# ZHSD-ETHERNET.net
KiCad netlist of a schematic drawn in Altium Designer
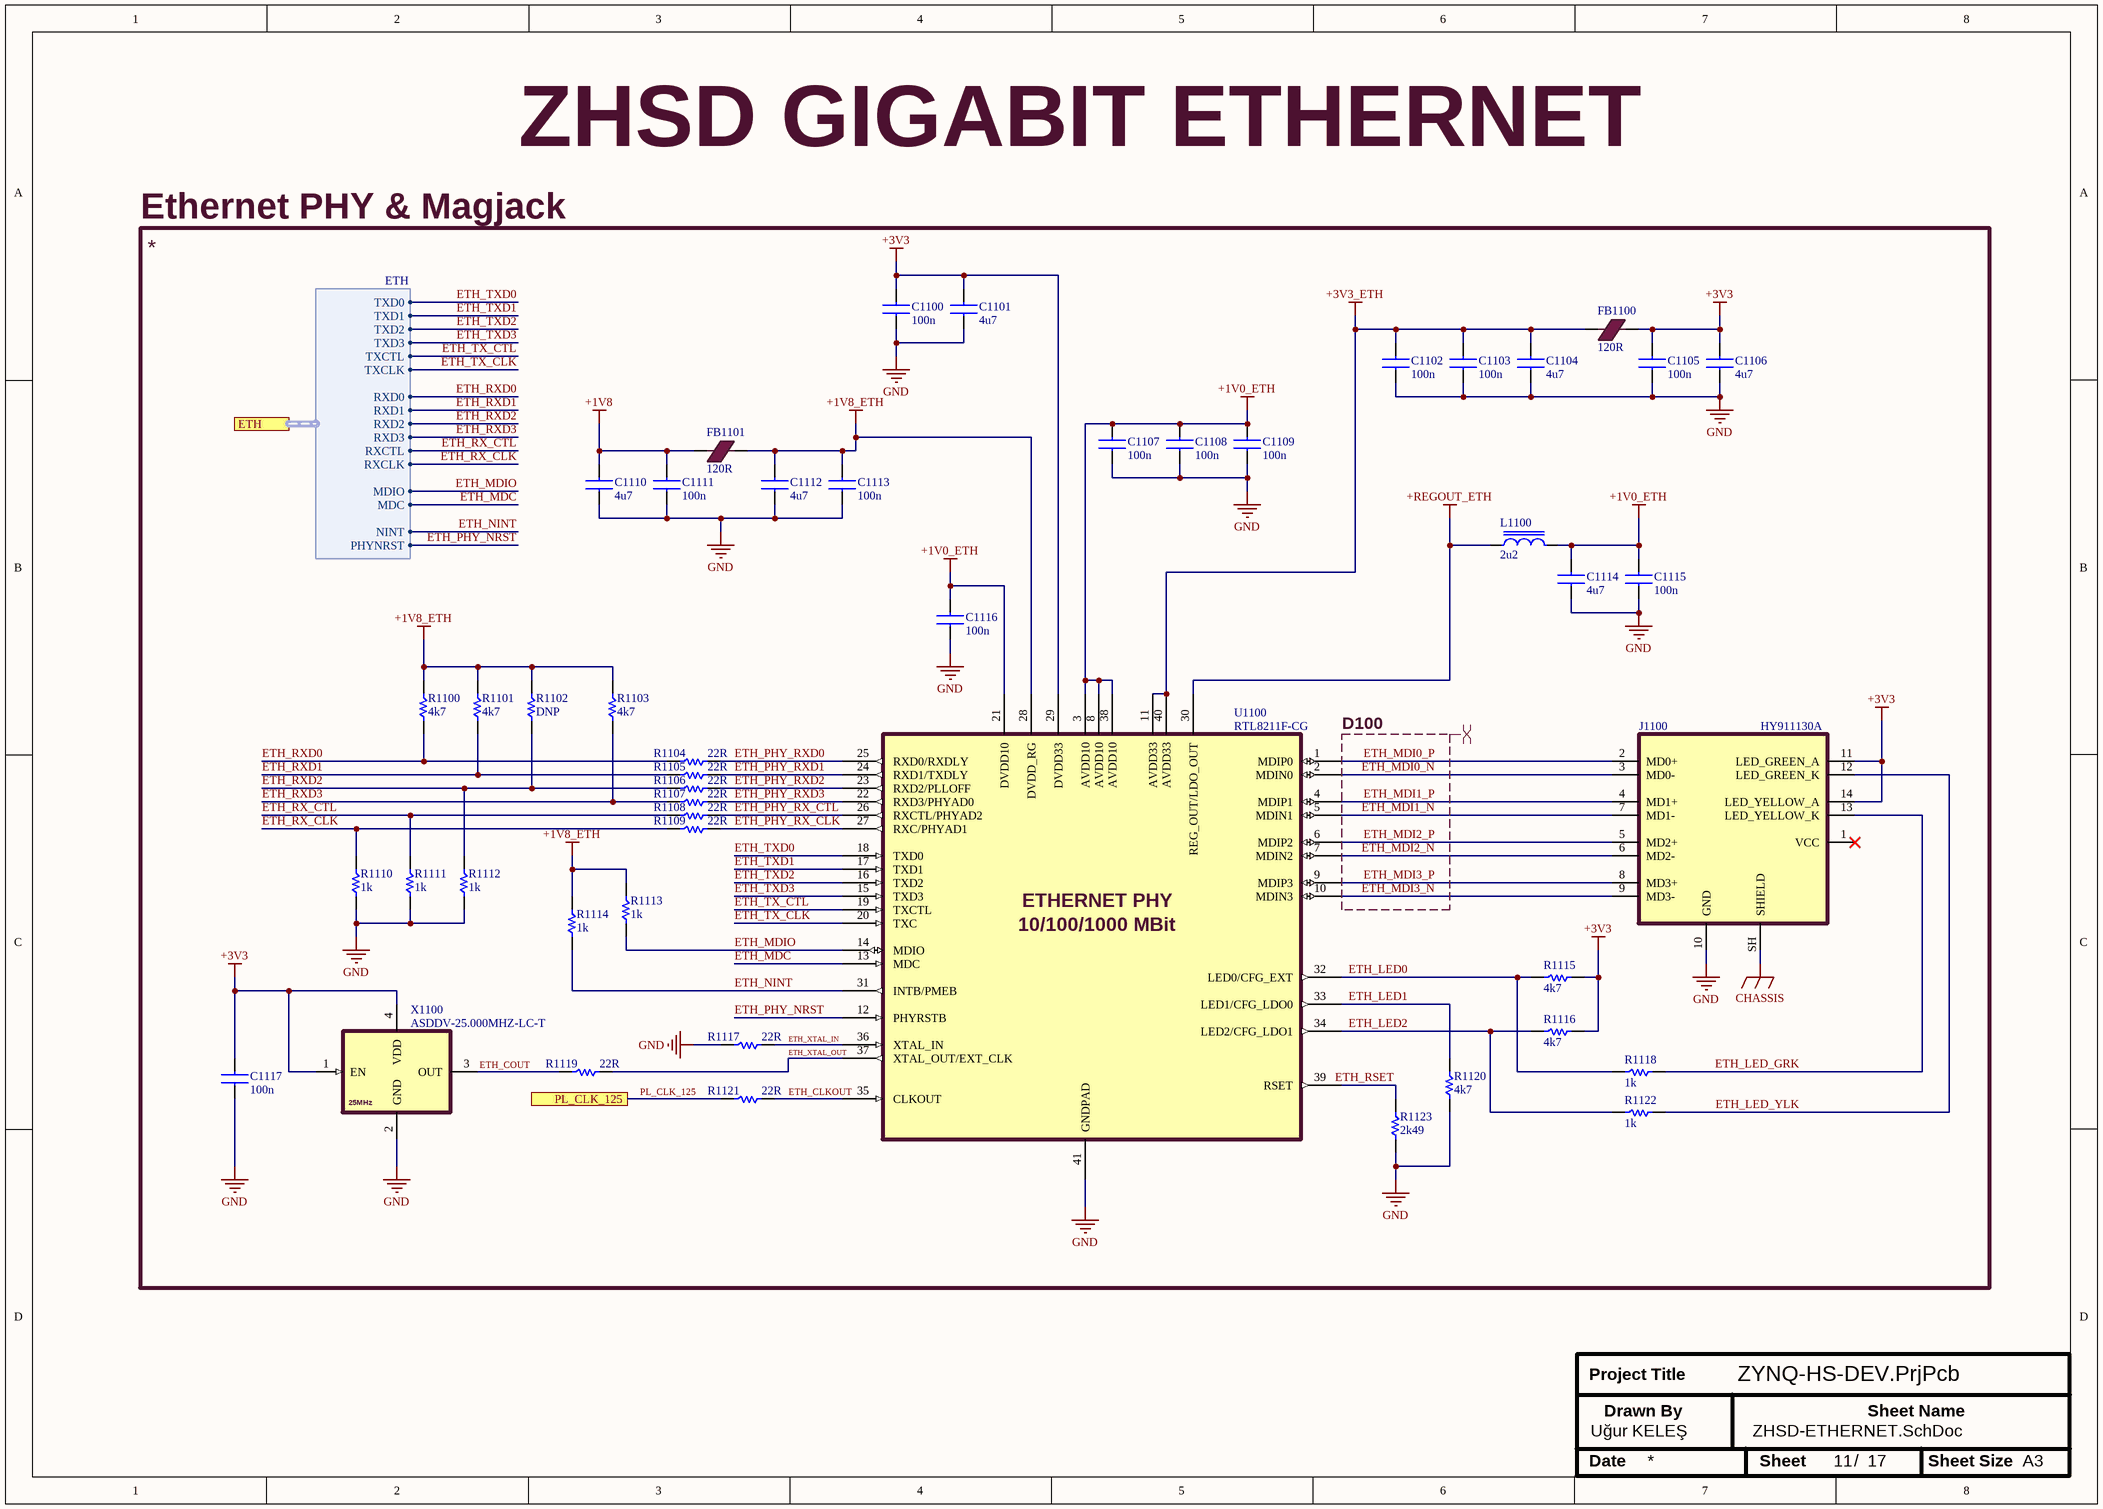
[diagram p0: ZHSD-ETHERNET.SchDoc]

(export (version "E")
  (design (tool "Eeschema 10.0.6"))
  (components
    (comp (ref "C1100")
      (value "100n")
      (footprint "0603CAPC1608X09N")
      (description "CAP CER 0.1UF 16V X7R 0402 (1005) ±10%")
      (fields (field (name "MANUFACTURER") "Murata Electronics") (field (name "MPN") "GRM155R71C104KA88J"))
      (libsource (lib "UK_Library") (part "GRM155R71C104KA88J"))
    )
    (comp (ref "C1101")
      (value "4u7")
      (footprint "0603CAPC1608X09N")
      (description "CAP CER 4.7UF 10V X5R 0603 (1608) ±10%")
      (fields
        (field (name "MANUFACTURER") "Samsung Electro-Mechanics")
        (field (name "MPN") "CL10A475KP8NNNC")
      )
      (libsource (lib "UK_Library") (part "CL10A475KP8NNNC"))
    )
    (comp (ref "C1102")
      (value "100n")
      (footprint "0603CAPC1608X09N")
      (description "CAP CER 0.1UF 16V X7R 0402 (1005) ±10%")
      (fields (field (name "MANUFACTURER") "Murata Electronics") (field (name "MPN") "GRM155R71C104KA88J"))
      (libsource (lib "UK_Library") (part "GRM155R71C104KA88J"))
    )
    (comp (ref "C1103")
      (value "100n")
      (footprint "0603CAPC1608X09N")
      (description "CAP CER 0.1UF 16V X7R 0402 (1005) ±10%")
      (fields (field (name "MANUFACTURER") "Murata Electronics") (field (name "MPN") "GRM155R71C104KA88J"))
      (libsource (lib "UK_Library") (part "GRM155R71C104KA88J"))
    )
    (comp (ref "C1104")
      (value "4u7")
      (footprint "0603CAPC1608X09N")
      (description "CAP CER 4.7UF 10V X5R 0603 (1608) ±10%")
      (fields
        (field (name "MANUFACTURER") "Samsung Electro-Mechanics")
        (field (name "MPN") "CL10A475KP8NNNC")
      )
      (libsource (lib "UK_Library") (part "CL10A475KP8NNNC"))
    )
    (comp (ref "C1105")
      (value "100n")
      (footprint "0603CAPC1608X09N")
      (description "CAP CER 0.1UF 16V X7R 0402 (1005) ±10%")
      (fields (field (name "MANUFACTURER") "Murata Electronics") (field (name "MPN") "GRM155R71C104KA88J"))
      (libsource (lib "UK_Library") (part "GRM155R71C104KA88J"))
    )
    (comp (ref "C1106")
      (value "4u7")
      (footprint "0603CAPC1608X09N")
      (description "CAP CER 4.7UF 10V X5R 0603 (1608) ±10%")
      (fields
        (field (name "MANUFACTURER") "Samsung Electro-Mechanics")
        (field (name "MPN") "CL10A475KP8NNNC")
      )
      (libsource (lib "UK_Library") (part "CL10A475KP8NNNC"))
    )
    (comp (ref "C1107")
      (value "100n")
      (footprint "0603CAPC1608X09N")
      (description "CAP CER 0.1UF 16V X7R 0402 (1005) ±10%")
      (fields (field (name "MANUFACTURER") "Murata Electronics") (field (name "MPN") "GRM155R71C104KA88J"))
      (libsource (lib "UK_Library") (part "GRM155R71C104KA88J"))
    )
    (comp (ref "C1108")
      (value "100n")
      (footprint "0603CAPC1608X09N")
      (description "CAP CER 0.1UF 16V X7R 0402 (1005) ±10%")
      (fields (field (name "MANUFACTURER") "Murata Electronics") (field (name "MPN") "GRM155R71C104KA88J"))
      (libsource (lib "UK_Library") (part "GRM155R71C104KA88J"))
    )
    (comp (ref "C1109")
      (value "100n")
      (footprint "0603CAPC1608X09N")
      (description "CAP CER 0.1UF 16V X7R 0402 (1005) ±10%")
      (fields (field (name "MANUFACTURER") "Murata Electronics") (field (name "MPN") "GRM155R71C104KA88J"))
      (libsource (lib "UK_Library") (part "GRM155R71C104KA88J"))
    )
    (comp (ref "C1110")
      (value "4u7")
      (footprint "0603CAPC1608X09N")
      (description "CAP CER 4.7UF 10V X5R 0603 (1608) ±10%")
      (fields
        (field (name "MANUFACTURER") "Samsung Electro-Mechanics")
        (field (name "MPN") "CL10A475KP8NNNC")
      )
      (libsource (lib "UK_Library") (part "CL10A475KP8NNNC"))
    )
    (comp (ref "C1111")
      (value "100n")
      (footprint "0603CAPC1608X09N")
      (description "CAP CER 0.1UF 16V X7R 0402 (1005) ±10%")
      (fields (field (name "MANUFACTURER") "Murata Electronics") (field (name "MPN") "GRM155R71C104KA88J"))
      (libsource (lib "UK_Library") (part "GRM155R71C104KA88J"))
    )
    (comp (ref "C1112")
      (value "4u7")
      (footprint "0603CAPC1608X09N")
      (description "CAP CER 4.7UF 10V X5R 0603 (1608) ±10%")
      (fields
        (field (name "MANUFACTURER") "Samsung Electro-Mechanics")
        (field (name "MPN") "CL10A475KP8NNNC")
      )
      (libsource (lib "UK_Library") (part "CL10A475KP8NNNC"))
    )
    (comp (ref "C1113")
      (value "100n")
      (footprint "0603CAPC1608X09N")
      (description "CAP CER 0.1UF 16V X7R 0402 (1005) ±10%")
      (fields (field (name "MANUFACTURER") "Murata Electronics") (field (name "MPN") "GRM155R71C104KA88J"))
      (libsource (lib "UK_Library") (part "GRM155R71C104KA88J"))
    )
    (comp (ref "C1114")
      (value "4u7")
      (footprint "0603CAPC1608X09N")
      (description "CAP CER 4.7UF 10V X5R 0603 (1608) ±10%")
      (fields
        (field (name "MANUFACTURER") "Samsung Electro-Mechanics")
        (field (name "MPN") "CL10A475KP8NNNC")
      )
      (libsource (lib "UK_Library") (part "CL10A475KP8NNNC"))
    )
    (comp (ref "C1115")
      (value "100n")
      (footprint "0603CAPC1608X09N")
      (description "CAP CER 0.1UF 16V X7R 0402 (1005) ±10%")
      (fields (field (name "MANUFACTURER") "Murata Electronics") (field (name "MPN") "GRM155R71C104KA88J"))
      (libsource (lib "UK_Library") (part "GRM155R71C104KA88J"))
    )
    (comp (ref "C1116")
      (value "100n")
      (footprint "0603CAPC1608X09N")
      (description "CAP CER 0.1UF 16V X7R 0402 (1005) ±10%")
      (fields (field (name "MANUFACTURER") "Murata Electronics") (field (name "MPN") "GRM155R71C104KA88J"))
      (libsource (lib "UK_Library") (part "GRM155R71C104KA88J"))
    )
    (comp (ref "C1117")
      (value "100n")
      (footprint "0603CAPC1608X09N")
      (description "CAP CER 0.1UF 50V X7R 0603 (1608) ±10%")
      (fields (field (name "MANUFACTURER") "KEMET") (field (name "MPN") "C0603C104K5RACTU"))
      (libsource (lib "UK_Library") (part "C0603C104K5RACTU"))
    )
    (comp (ref "FB1100")
      (value "120R")
      (footprint "0603INDC1608X08N")
      (description "FERRITE BEAD 120 OHM 0603 (1608) 3A 25mOhm")
      (fields (field (name "MANUFACTURER") "Murata Electronics") (field (name "MPN") "BLM18SG121TN1D"))
      (libsource (lib "UK_Library") (part "BLM18SG121TN1D"))
    )
    (comp (ref "FB1101")
      (value "120R")
      (footprint "0603INDC1608X08N")
      (description "FERRITE BEAD 120 OHM 0603 (1608) 3A 25mOhm")
      (fields (field (name "MANUFACTURER") "Murata Electronics") (field (name "MPN") "BLM18SG121TN1D"))
      (libsource (lib "UK_Library") (part "BLM18SG121TN1D"))
    )
    (comp (ref "J1100")
      (value "HY911130A")
      (footprint "HY911130A")
      (description "Jack Modular Connector RJ45 Through Hole Shielded")
      (fields (field (name "MANUFACTURER") "Hanrun"))
      (libsource (lib "UK_Library") (part "HY911130A"))
    )
    (comp (ref "L1100")
      (value "2u2")
      (footprint "0603INDC1608X08N")
      (description "FIXED IND 2.2UH 1.05A 250 MOHM 0603 (1608 Metric)")
      (fields (field (name "MANUFACTURER") "Murata Electronics") (field (name "MPN") "LQM18PN2R2MGHD"))
      (libsource (lib "UK_Library") (part "LQM18PN2R2MGHD"))
    )
    (comp (ref "R1100")
      (value "4k7")
      (footprint "0402RESC1005X04N")
      (description "RES 4.7K OHM 5% 1/16W 0402 (1005)")
      (fields (field (name "MANUFACTURER") "YAGEO") (field (name "MPN") "RT0402FRE0780RL"))
      (libsource (lib "UK_Library") (part "RC0402JR-074K7L"))
    )
    (comp (ref "R1101")
      (value "4k7")
      (footprint "0402RESC1005X04N")
      (description "RES 4.7K OHM 5% 1/16W 0402 (1005)")
      (fields (field (name "MANUFACTURER") "YAGEO") (field (name "MPN") "RT0402FRE0780RL"))
      (libsource (lib "UK_Library") (part "RC0402JR-074K7L"))
    )
    (comp (ref "R1102")
      (value "DNP")
      (footprint "0402RESC1005X04N")
      (description "DO NOT POPULATE RESISTOR")
      (fields (field (name "MANUFACTURER") "***"))
      (libsource (lib "UK_Library") (part "DNP_RES"))
    )
    (comp (ref "R1103")
      (value "4k7")
      (footprint "0402RESC1005X04N")
      (description "RES 4.7K OHM 5% 1/16W 0402 (1005)")
      (fields (field (name "MANUFACTURER") "YAGEO") (field (name "MPN") "RT0402FRE0780RL"))
      (libsource (lib "UK_Library") (part "RC0402JR-074K7L"))
    )
    (comp (ref "R1104")
      (value "22R")
      (footprint "0603RESC1608X05N")
      (description "RES 22 OHM 1% 1/10W 0603 (1608)")
      (fields (field (name "MANUFACTURER") "YAGEO") (field (name "MPN") "RC0603FR-0722RL"))
      (libsource (lib "UK_Library") (part "RC0603FR-0722RL"))
    )
    (comp (ref "R1105")
      (value "22R")
      (footprint "0603RESC1608X05N")
      (description "RES 22 OHM 1% 1/10W 0603 (1608)")
      (fields (field (name "MANUFACTURER") "YAGEO") (field (name "MPN") "RC0603FR-0722RL"))
      (libsource (lib "UK_Library") (part "RC0603FR-0722RL"))
    )
    (comp (ref "R1106")
      (value "22R")
      (footprint "0603RESC1608X05N")
      (description "RES 22 OHM 1% 1/10W 0603 (1608)")
      (fields (field (name "MANUFACTURER") "YAGEO") (field (name "MPN") "RC0603FR-0722RL"))
      (libsource (lib "UK_Library") (part "RC0603FR-0722RL"))
    )
    (comp (ref "R1107")
      (value "22R")
      (footprint "0603RESC1608X05N")
      (description "RES 22 OHM 1% 1/10W 0603 (1608)")
      (fields (field (name "MANUFACTURER") "YAGEO") (field (name "MPN") "RC0603FR-0722RL"))
      (libsource (lib "UK_Library") (part "RC0603FR-0722RL"))
    )
    (comp (ref "R1108")
      (value "22R")
      (footprint "0603RESC1608X05N")
      (description "RES 22 OHM 1% 1/10W 0603 (1608)")
      (fields (field (name "MANUFACTURER") "YAGEO") (field (name "MPN") "RC0603FR-0722RL"))
      (libsource (lib "UK_Library") (part "RC0603FR-0722RL"))
    )
    (comp (ref "R1109")
      (value "22R")
      (footprint "0603RESC1608X05N")
      (description "RES 22 OHM 1% 1/10W 0603 (1608)")
      (fields (field (name "MANUFACTURER") "YAGEO") (field (name "MPN") "RC0603FR-0722RL"))
      (libsource (lib "UK_Library") (part "RC0603FR-0722RL"))
    )
    (comp (ref "R1110")
      (value "1k")
      (footprint "0402RESC1005X04N")
      (description "RES 1K OHM 5% 1/16W 0402 (1005)")
      (fields (field (name "MANUFACTURER") "YAGEO") (field (name "MPN") "RC0402JR-071KL"))
      (libsource (lib "UK_Library") (part "RC0402JR-071KL"))
    )
    (comp (ref "R1111")
      (value "1k")
      (footprint "0402RESC1005X04N")
      (description "RES 1K OHM 5% 1/16W 0402 (1005)")
      (fields (field (name "MANUFACTURER") "YAGEO") (field (name "MPN") "RC0402JR-071KL"))
      (libsource (lib "UK_Library") (part "RC0402JR-071KL"))
    )
    (comp (ref "R1112")
      (value "1k")
      (footprint "0402RESC1005X04N")
      (description "RES 1K OHM 5% 1/16W 0402 (1005)")
      (fields (field (name "MANUFACTURER") "YAGEO") (field (name "MPN") "RC0402JR-071KL"))
      (libsource (lib "UK_Library") (part "RC0402JR-071KL"))
    )
    (comp (ref "R1113")
      (value "1k")
      (footprint "0402RESC1005X04N")
      (description "RES 1K OHM 5% 1/16W 0402 (1005)")
      (fields (field (name "MANUFACTURER") "YAGEO") (field (name "MPN") "RC0402JR-071KL"))
      (libsource (lib "UK_Library") (part "RC0402JR-071KL"))
    )
    (comp (ref "R1114")
      (value "1k")
      (footprint "0402RESC1005X04N")
      (description "RES 1K OHM 5% 1/16W 0402 (1005)")
      (fields (field (name "MANUFACTURER") "YAGEO") (field (name "MPN") "RC0402JR-071KL"))
      (libsource (lib "UK_Library") (part "RC0402JR-071KL"))
    )
    (comp (ref "R1115")
      (value "4k7")
      (footprint "0402RESC1005X04N")
      (description "RES 4.7K OHM 5% 1/16W 0402 (1005)")
      (fields (field (name "MANUFACTURER") "YAGEO") (field (name "MPN") "RT0402FRE0780RL"))
      (libsource (lib "UK_Library") (part "RC0402JR-074K7L"))
    )
    (comp (ref "R1116")
      (value "4k7")
      (footprint "0402RESC1005X04N")
      (description "RES 4.7K OHM 5% 1/16W 0402 (1005)")
      (fields (field (name "MANUFACTURER") "YAGEO") (field (name "MPN") "RT0402FRE0780RL"))
      (libsource (lib "UK_Library") (part "RC0402JR-074K7L"))
    )
    (comp (ref "R1117")
      (value "22R")
      (footprint "0603RESC1608X05N")
      (description "RES 22 OHM 1% 1/10W 0603 (1608)")
      (fields (field (name "MANUFACTURER") "YAGEO") (field (name "MPN") "RC0603FR-0722RL"))
      (libsource (lib "UK_Library") (part "RC0603FR-0722RL"))
    )
    (comp (ref "R1118")
      (value "1k")
      (footprint "0402RESC1005X04N")
      (description "RES 1K OHM 5% 1/16W 0402 (1005)")
      (fields (field (name "MANUFACTURER") "YAGEO") (field (name "MPN") "RC0402JR-071KL"))
      (libsource (lib "UK_Library") (part "RC0402JR-071KL"))
    )
    (comp (ref "R1119")
      (value "22R")
      (footprint "0603RESC1608X05N")
      (description "RES 22 OHM 1% 1/10W 0603 (1608)")
      (fields (field (name "MANUFACTURER") "YAGEO") (field (name "MPN") "RC0603FR-0722RL"))
      (libsource (lib "UK_Library") (part "RC0603FR-0722RL"))
    )
    (comp (ref "R1120")
      (value "4k7")
      (footprint "0402RESC1005X04N")
      (description "RES 4.7K OHM 5% 1/16W 0402 (1005)")
      (fields (field (name "MANUFACTURER") "YAGEO") (field (name "MPN") "RT0402FRE0780RL"))
      (libsource (lib "UK_Library") (part "RC0402JR-074K7L"))
    )
    (comp (ref "R1121")
      (value "22R")
      (footprint "0603RESC1608X05N")
      (description "RES 22 OHM 1% 1/10W 0603 (1608)")
      (fields (field (name "MANUFACTURER") "YAGEO") (field (name "MPN") "RC0603FR-0722RL"))
      (libsource (lib "UK_Library") (part "RC0603FR-0722RL"))
    )
    (comp (ref "R1122")
      (value "1k")
      (footprint "0402RESC1005X04N")
      (description "RES 1K OHM 5% 1/16W 0402 (1005)")
      (fields (field (name "MANUFACTURER") "YAGEO") (field (name "MPN") "RC0402JR-071KL"))
      (libsource (lib "UK_Library") (part "RC0402JR-071KL"))
    )
    (comp (ref "R1123")
      (value "2k49")
      (footprint "0402RESC1005X04N")
      (description "RES 2.49K OHM 1% 1/16W 0402 (1005)")
      (fields (field (name "MANUFACTURER") "YAGEO") (field (name "MPN") "RC0402FR-132K49L"))
      (libsource (lib "UK_Library") (part "RC0402FR-132K49L"))
    )
    (comp (ref "U1100")
      (value "RTL8211F-CG")
      (footprint "QFN40P500X500X90_HS-41N")
      (description "RGMII Ethernet Transceiver WQFN-40-EP(5x5) Drivers, Receivers, Transceivers RoHS")
      (fields (field (name "MANUFACTURER") "REALTEK"))
      (libsource (lib "UK_Library") (part "RTL8211F-CG"))
    )
    (comp (ref "X1100")
      (value "ASDDV-25.000MHZ-LC-T")
      (footprint "XTAL_2520")
      (description "25 MHz XO (Standard) HCMOS, LVCMOS Oscillator 1.6V ~ 3.6V Enable/Disable 4-SMD, No Lead")
      (fields (field (name "MANUFACTURER") "Abracon LLC"))
      (libsource (lib "UK_Library") (part "ASDDV-25.000MHZ-LC-T"))
    )
  )
  (nets
    (net (code "2") (name "+1V0_ETH") (class "Default")
      (node (ref "C1107") (pin "2") (pinfunction "2_2") (pintype "passive"))
      (node (ref "C1108") (pin "2") (pinfunction "2_2") (pintype "passive"))
      (node (ref "C1109") (pin "2") (pinfunction "2_2") (pintype "passive"))
      (node (ref "C1114") (pin "2") (pinfunction "2_2") (pintype "passive"))
      (node (ref "C1115") (pin "2") (pinfunction "2_2") (pintype "passive"))
      (node (ref "C1116") (pin "2") (pinfunction "2_2") (pintype "passive"))
      (node (ref "L1100") (pin "2") (pinfunction "2_2") (pintype "passive"))
      (node (ref "U1100") (pin "21") (pinfunction "_DVDD10_21") (pintype "power_in"))
      (node (ref "U1100") (pin "3") (pinfunction "_AVDD10_3") (pintype "power_in"))
      (node (ref "U1100") (pin "38") (pinfunction "_AVDD10_38") (pintype "power_in"))
      (node (ref "U1100") (pin "8") (pinfunction "_AVDD10_8") (pintype "power_in"))
    )
    (net (code "3") (name "+1V8") (class "Default")
      (node (ref "C1110") (pin "2") (pinfunction "2_2") (pintype "passive"))
      (node (ref "C1111") (pin "2") (pinfunction "2_2") (pintype "passive"))
      (node (ref "FB1101") (pin "1") (pinfunction "1_1") (pintype "passive"))
    )
    (net (code "4") (name "+1V8_ETH") (class "Default")
      (node (ref "C1112") (pin "2") (pinfunction "2_2") (pintype "passive"))
      (node (ref "C1113") (pin "2") (pinfunction "2_2") (pintype "passive"))
      (node (ref "FB1101") (pin "2") (pinfunction "2_2") (pintype "passive"))
      (node (ref "R1100") (pin "2") (pinfunction "2_2") (pintype "passive"))
      (node (ref "R1101") (pin "2") (pinfunction "2_2") (pintype "passive"))
      (node (ref "R1102") (pin "2") (pinfunction "2_2") (pintype "passive"))
      (node (ref "R1103") (pin "2") (pinfunction "2_2") (pintype "passive"))
      (node (ref "R1113") (pin "2") (pinfunction "2_2") (pintype "passive"))
      (node (ref "R1114") (pin "2") (pinfunction "2_2") (pintype "passive"))
      (node (ref "U1100") (pin "28") (pinfunction "_DVDD_RG_28") (pintype "power_in"))
    )
    (net (code "5") (name "+3V3") (class "Default")
      (node (ref "C1100") (pin "2") (pinfunction "2_2") (pintype "passive"))
      (node (ref "C1101") (pin "2") (pinfunction "2_2") (pintype "passive"))
      (node (ref "C1105") (pin "2") (pinfunction "2_2") (pintype "passive"))
      (node (ref "C1106") (pin "2") (pinfunction "2_2") (pintype "passive"))
      (node (ref "C1117") (pin "2") (pinfunction "2_2") (pintype "passive"))
      (node (ref "FB1100") (pin "2") (pinfunction "2_2") (pintype "passive"))
      (node (ref "J1100") (pin "11") (pinfunction "LED_GREEN_A_11") (pintype "passive"))
      (node (ref "J1100") (pin "14") (pinfunction "LED_YELLOW_A_14") (pintype "passive"))
      (node (ref "R1115") (pin "1") (pinfunction "1_1") (pintype "passive"))
      (node (ref "R1116") (pin "1") (pinfunction "1_1") (pintype "passive"))
      (node (ref "U1100") (pin "29") (pinfunction "_DVDD33_29") (pintype "power_in"))
      (node (ref "X1100") (pin "1") (pinfunction "EN_1") (pintype "input"))
      (node (ref "X1100") (pin "4") (pinfunction "VDD_4") (pintype "power_in"))
    )
    (net (code "6") (name "+3V3_ETH") (class "Default")
      (node (ref "C1102") (pin "2") (pinfunction "2_2") (pintype "passive"))
      (node (ref "C1103") (pin "2") (pinfunction "2_2") (pintype "passive"))
      (node (ref "C1104") (pin "2") (pinfunction "2_2") (pintype "passive"))
      (node (ref "FB1100") (pin "1") (pinfunction "1_1") (pintype "passive"))
      (node (ref "U1100") (pin "11") (pinfunction "_AVDD33_11") (pintype "power_in"))
      (node (ref "U1100") (pin "40") (pinfunction "_AVDD33_40") (pintype "power_in"))
    )
    (net (code "7") (name "+REGOUT_ETH") (class "Default")
      (node (ref "L1100") (pin "1") (pinfunction "1_1") (pintype "passive"))
      (node (ref "U1100") (pin "30") (pinfunction "_REG_OUT/LDO_OUT_30") (pintype "power_in"))
    )
    (net (code "8") (name "/ETH_CLKOUT") (class "Default")
      (node (ref "R1121") (pin "1") (pinfunction "1_1") (pintype "passive"))
      (node (ref "U1100") (pin "35") (pinfunction "_CLKOUT_35") (pintype "input"))
    )
    (net (code "9") (name "/ETH_COUT") (class "Default")
      (node (ref "R1119") (pin "2") (pinfunction "2_2") (pintype "passive"))
      (node (ref "X1100") (pin "3") (pinfunction "OUT_3") (pintype "passive"))
    )
    (net (code "10") (name "/ETH_LED0") (class "Default")
      (node (ref "R1115") (pin "2") (pinfunction "2_2") (pintype "passive"))
      (node (ref "R1118") (pin "2") (pinfunction "2_2") (pintype "passive"))
      (node (ref "U1100") (pin "32") (pinfunction "_LED0/CFG_EXT_32") (pintype "output"))
    )
    (net (code "11") (name "/ETH_LED1") (class "Default")
      (node (ref "R1120") (pin "2") (pinfunction "2_2") (pintype "passive"))
      (node (ref "U1100") (pin "33") (pinfunction "_LED1/CFG_LDO0_33") (pintype "output"))
    )
    (net (code "12") (name "/ETH_LED2") (class "Default")
      (node (ref "R1116") (pin "2") (pinfunction "2_2") (pintype "passive"))
      (node (ref "R1122") (pin "2") (pinfunction "2_2") (pintype "passive"))
      (node (ref "U1100") (pin "34") (pinfunction "_LED2/CFG_LDO1_34") (pintype "output"))
    )
    (net (code "13") (name "/ETH_LED_GRK") (class "Default")
      (node (ref "J1100") (pin "13") (pinfunction "LED_YELLOW_K_13") (pintype "passive"))
      (node (ref "R1118") (pin "1") (pinfunction "1_1") (pintype "passive"))
    )
    (net (code "14") (name "/ETH_LED_YLK") (class "Default")
      (node (ref "J1100") (pin "12") (pinfunction "LED_GREEN_K_12") (pintype "passive"))
      (node (ref "R1122") (pin "1") (pinfunction "1_1") (pintype "passive"))
    )
    (net (code "15") (name "/ETH_MDC") (class "Default")
      (node (ref "U1100") (pin "13") (pinfunction "_MDC_13") (pintype "input"))
    )
    (net (code "16") (name "/ETH_MDI0_N") (class "Default")
      (node (ref "J1100") (pin "3") (pinfunction "MD0-_3") (pintype "passive"))
      (node (ref "U1100") (pin "2") (pinfunction "_MDIN0_2") (pintype "bidirectional"))
    )
    (net (code "17") (name "/ETH_MDI0_P") (class "Default")
      (node (ref "J1100") (pin "2") (pinfunction "MD0+_2") (pintype "passive"))
      (node (ref "U1100") (pin "1") (pinfunction "_MDIP0_1") (pintype "bidirectional"))
    )
    (net (code "18") (name "/ETH_MDI1_N") (class "Default")
      (node (ref "J1100") (pin "7") (pinfunction "MD1-_7") (pintype "passive"))
      (node (ref "U1100") (pin "5") (pinfunction "_MDIN1_5") (pintype "bidirectional"))
    )
    (net (code "19") (name "/ETH_MDI1_P") (class "Default")
      (node (ref "J1100") (pin "4") (pinfunction "MD1+_4") (pintype "passive"))
      (node (ref "U1100") (pin "4") (pinfunction "_MDIP1_4") (pintype "bidirectional"))
    )
    (net (code "20") (name "/ETH_MDI2_N") (class "Default")
      (node (ref "J1100") (pin "6") (pinfunction "MD2-_6") (pintype "passive"))
      (node (ref "U1100") (pin "7") (pinfunction "_MDIN2_7") (pintype "bidirectional"))
    )
    (net (code "21") (name "/ETH_MDI2_P") (class "Default")
      (node (ref "J1100") (pin "5") (pinfunction "MD2+_5") (pintype "passive"))
      (node (ref "U1100") (pin "6") (pinfunction "_MDIP2_6") (pintype "bidirectional"))
    )
    (net (code "22") (name "/ETH_MDI3_N") (class "Default")
      (node (ref "J1100") (pin "9") (pinfunction "MD3-_9") (pintype "passive"))
      (node (ref "U1100") (pin "10") (pinfunction "_MDIN3_10") (pintype "bidirectional"))
    )
    (net (code "23") (name "/ETH_MDI3_P") (class "Default")
      (node (ref "J1100") (pin "8") (pinfunction "MD3+_8") (pintype "passive"))
      (node (ref "U1100") (pin "9") (pinfunction "_MDIP3_9") (pintype "bidirectional"))
    )
    (net (code "24") (name "/ETH_MDIO") (class "Default")
      (node (ref "R1113") (pin "1") (pinfunction "1_1") (pintype "passive"))
      (node (ref "U1100") (pin "14") (pinfunction "_MDIO_14") (pintype "bidirectional"))
    )
    (net (code "25") (name "/ETH_NINT") (class "Default")
      (node (ref "R1114") (pin "1") (pinfunction "1_1") (pintype "passive"))
      (node (ref "U1100") (pin "31") (pinfunction "_INTB/PMEB_31") (pintype "output"))
    )
    (net (code "26") (name "/ETH_PHY_NRST") (class "Default")
      (node (ref "U1100") (pin "12") (pinfunction "_PHYRSTB_12") (pintype "input"))
    )
    (net (code "27") (name "/ETH_PHY_RXD0") (class "Default")
      (node (ref "R1104") (pin "1") (pinfunction "1_1") (pintype "passive"))
      (node (ref "U1100") (pin "25") (pinfunction "_RXD0/RXDLY_25") (pintype "output"))
    )
    (net (code "28") (name "/ETH_PHY_RXD1") (class "Default")
      (node (ref "R1105") (pin "1") (pinfunction "1_1") (pintype "passive"))
      (node (ref "U1100") (pin "24") (pinfunction "_RXD1/TXDLY_24") (pintype "output"))
    )
    (net (code "29") (name "/ETH_PHY_RXD2") (class "Default")
      (node (ref "R1106") (pin "1") (pinfunction "1_1") (pintype "passive"))
      (node (ref "U1100") (pin "23") (pinfunction "_RXD2/PLLOFF_23") (pintype "output"))
    )
    (net (code "30") (name "/ETH_PHY_RXD3") (class "Default")
      (node (ref "R1107") (pin "1") (pinfunction "1_1") (pintype "passive"))
      (node (ref "U1100") (pin "22") (pinfunction "_RXD3/PHYAD0_22") (pintype "output"))
    )
    (net (code "31") (name "/ETH_PHY_RX_CLK") (class "Default")
      (node (ref "R1109") (pin "1") (pinfunction "1_1") (pintype "passive"))
      (node (ref "U1100") (pin "27") (pinfunction "_RXC/PHYAD1_27") (pintype "output"))
    )
    (net (code "32") (name "/ETH_PHY_RX_CTL") (class "Default")
      (node (ref "R1108") (pin "1") (pinfunction "1_1") (pintype "passive"))
      (node (ref "U1100") (pin "26") (pinfunction "_RXCTL/PHYAD2_26") (pintype "output"))
    )
    (net (code "33") (name "/ETH_RSET") (class "Default")
      (node (ref "R1123") (pin "2") (pinfunction "2_2") (pintype "passive"))
      (node (ref "U1100") (pin "39") (pinfunction "_RSET_39") (pintype "output"))
    )
    (net (code "34") (name "/ETH_RXD0") (class "Default")
      (node (ref "R1100") (pin "1") (pinfunction "1_1") (pintype "passive"))
      (node (ref "R1104") (pin "2") (pinfunction "2_2") (pintype "passive"))
    )
    (net (code "35") (name "/ETH_RXD1") (class "Default")
      (node (ref "R1101") (pin "1") (pinfunction "1_1") (pintype "passive"))
      (node (ref "R1105") (pin "2") (pinfunction "2_2") (pintype "passive"))
    )
    (net (code "36") (name "/ETH_RXD2") (class "Default")
      (node (ref "R1102") (pin "1") (pinfunction "1_1") (pintype "passive"))
      (node (ref "R1106") (pin "2") (pinfunction "2_2") (pintype "passive"))
      (node (ref "R1112") (pin "2") (pinfunction "2_2") (pintype "passive"))
    )
    (net (code "37") (name "/ETH_RXD3") (class "Default")
      (node (ref "R1103") (pin "1") (pinfunction "1_1") (pintype "passive"))
      (node (ref "R1107") (pin "2") (pinfunction "2_2") (pintype "passive"))
    )
    (net (code "38") (name "/ETH_RX_CLK") (class "Default")
      (node (ref "R1109") (pin "2") (pinfunction "2_2") (pintype "passive"))
      (node (ref "R1110") (pin "2") (pinfunction "2_2") (pintype "passive"))
    )
    (net (code "39") (name "/ETH_RX_CTL") (class "Default")
      (node (ref "R1108") (pin "2") (pinfunction "2_2") (pintype "passive"))
      (node (ref "R1111") (pin "2") (pinfunction "2_2") (pintype "passive"))
    )
    (net (code "40") (name "/ETH_TXD0") (class "Default")
      (node (ref "U1100") (pin "18") (pinfunction "_TXD0_18") (pintype "input"))
    )
    (net (code "41") (name "/ETH_TXD1") (class "Default")
      (node (ref "U1100") (pin "17") (pinfunction "_TXD1_17") (pintype "input"))
    )
    (net (code "42") (name "/ETH_TXD2") (class "Default")
      (node (ref "U1100") (pin "16") (pinfunction "_TXD2_16") (pintype "input"))
    )
    (net (code "43") (name "/ETH_TXD3") (class "Default")
      (node (ref "U1100") (pin "15") (pinfunction "_TXD3_15") (pintype "input"))
    )
    (net (code "44") (name "/ETH_TX_CLK") (class "Default")
      (node (ref "U1100") (pin "20") (pinfunction "_TXC_20") (pintype "input"))
    )
    (net (code "45") (name "/ETH_TX_CTL") (class "Default")
      (node (ref "U1100") (pin "19") (pinfunction "_TXCTL_19") (pintype "input"))
    )
    (net (code "46") (name "/ETH_XTAL_IN") (class "Default")
      (node (ref "R1117") (pin "1") (pinfunction "1_1") (pintype "passive"))
      (node (ref "U1100") (pin "36") (pinfunction "_XTAL_IN_36") (pintype "input"))
    )
    (net (code "47") (name "/ETH_XTAL_OUT") (class "Default")
      (node (ref "R1119") (pin "1") (pinfunction "1_1") (pintype "passive"))
      (node (ref "U1100") (pin "37") (pinfunction "_XTAL_OUT/EXT_CLK_37") (pintype "output"))
    )
    (net (code "48") (name "/PL_CLK_125") (class "Default")
      (node (ref "R1121") (pin "2") (pinfunction "2_2") (pintype "passive"))
    )
    (net (code "50") (name "CHASSIS") (class "Default")
      (node (ref "J1100") (pin "SH") (pinfunction "SHIELD_SH") (pintype "passive"))
    )
    (net (code "51") (name "GND") (class "Default")
      (node (ref "C1100") (pin "1") (pinfunction "1_1") (pintype "passive"))
      (node (ref "C1101") (pin "1") (pinfunction "1_1") (pintype "passive"))
      (node (ref "C1102") (pin "1") (pinfunction "1_1") (pintype "passive"))
      (node (ref "C1103") (pin "1") (pinfunction "1_1") (pintype "passive"))
      (node (ref "C1104") (pin "1") (pinfunction "1_1") (pintype "passive"))
      (node (ref "C1105") (pin "1") (pinfunction "1_1") (pintype "passive"))
      (node (ref "C1106") (pin "1") (pinfunction "1_1") (pintype "passive"))
      (node (ref "C1107") (pin "1") (pinfunction "1_1") (pintype "passive"))
      (node (ref "C1108") (pin "1") (pinfunction "1_1") (pintype "passive"))
      (node (ref "C1109") (pin "1") (pinfunction "1_1") (pintype "passive"))
      (node (ref "C1110") (pin "1") (pinfunction "1_1") (pintype "passive"))
      (node (ref "C1111") (pin "1") (pinfunction "1_1") (pintype "passive"))
      (node (ref "C1112") (pin "1") (pinfunction "1_1") (pintype "passive"))
      (node (ref "C1113") (pin "1") (pinfunction "1_1") (pintype "passive"))
      (node (ref "C1114") (pin "1") (pinfunction "1_1") (pintype "passive"))
      (node (ref "C1115") (pin "1") (pinfunction "1_1") (pintype "passive"))
      (node (ref "C1116") (pin "1") (pinfunction "1_1") (pintype "passive"))
      (node (ref "C1117") (pin "1") (pinfunction "1_1") (pintype "passive"))
      (node (ref "J1100") (pin "10") (pinfunction "GND_10") (pintype "passive"))
      (node (ref "R1110") (pin "1") (pinfunction "1_1") (pintype "passive"))
      (node (ref "R1111") (pin "1") (pinfunction "1_1") (pintype "passive"))
      (node (ref "R1112") (pin "1") (pinfunction "1_1") (pintype "passive"))
      (node (ref "R1117") (pin "2") (pinfunction "2_2") (pintype "passive"))
      (node (ref "R1120") (pin "1") (pinfunction "1_1") (pintype "passive"))
      (node (ref "R1123") (pin "1") (pinfunction "1_1") (pintype "passive"))
      (node (ref "U1100") (pin "41") (pinfunction "GNDPAD_41") (pintype "power_in"))
      (node (ref "X1100") (pin "2") (pinfunction "GND_2") (pintype "power_in"))
    )
    (net (code "52") (name "unconnected-(J1100-VCC-Pad1)") (class "Default")
      (node (ref "J1100") (pin "1") (pinfunction "VCC_1") (pintype "passive+no_connect"))
    )
  )
)
